# CalibrationBoard.net
KiCad netlist of a schematic drawn in EAGLE
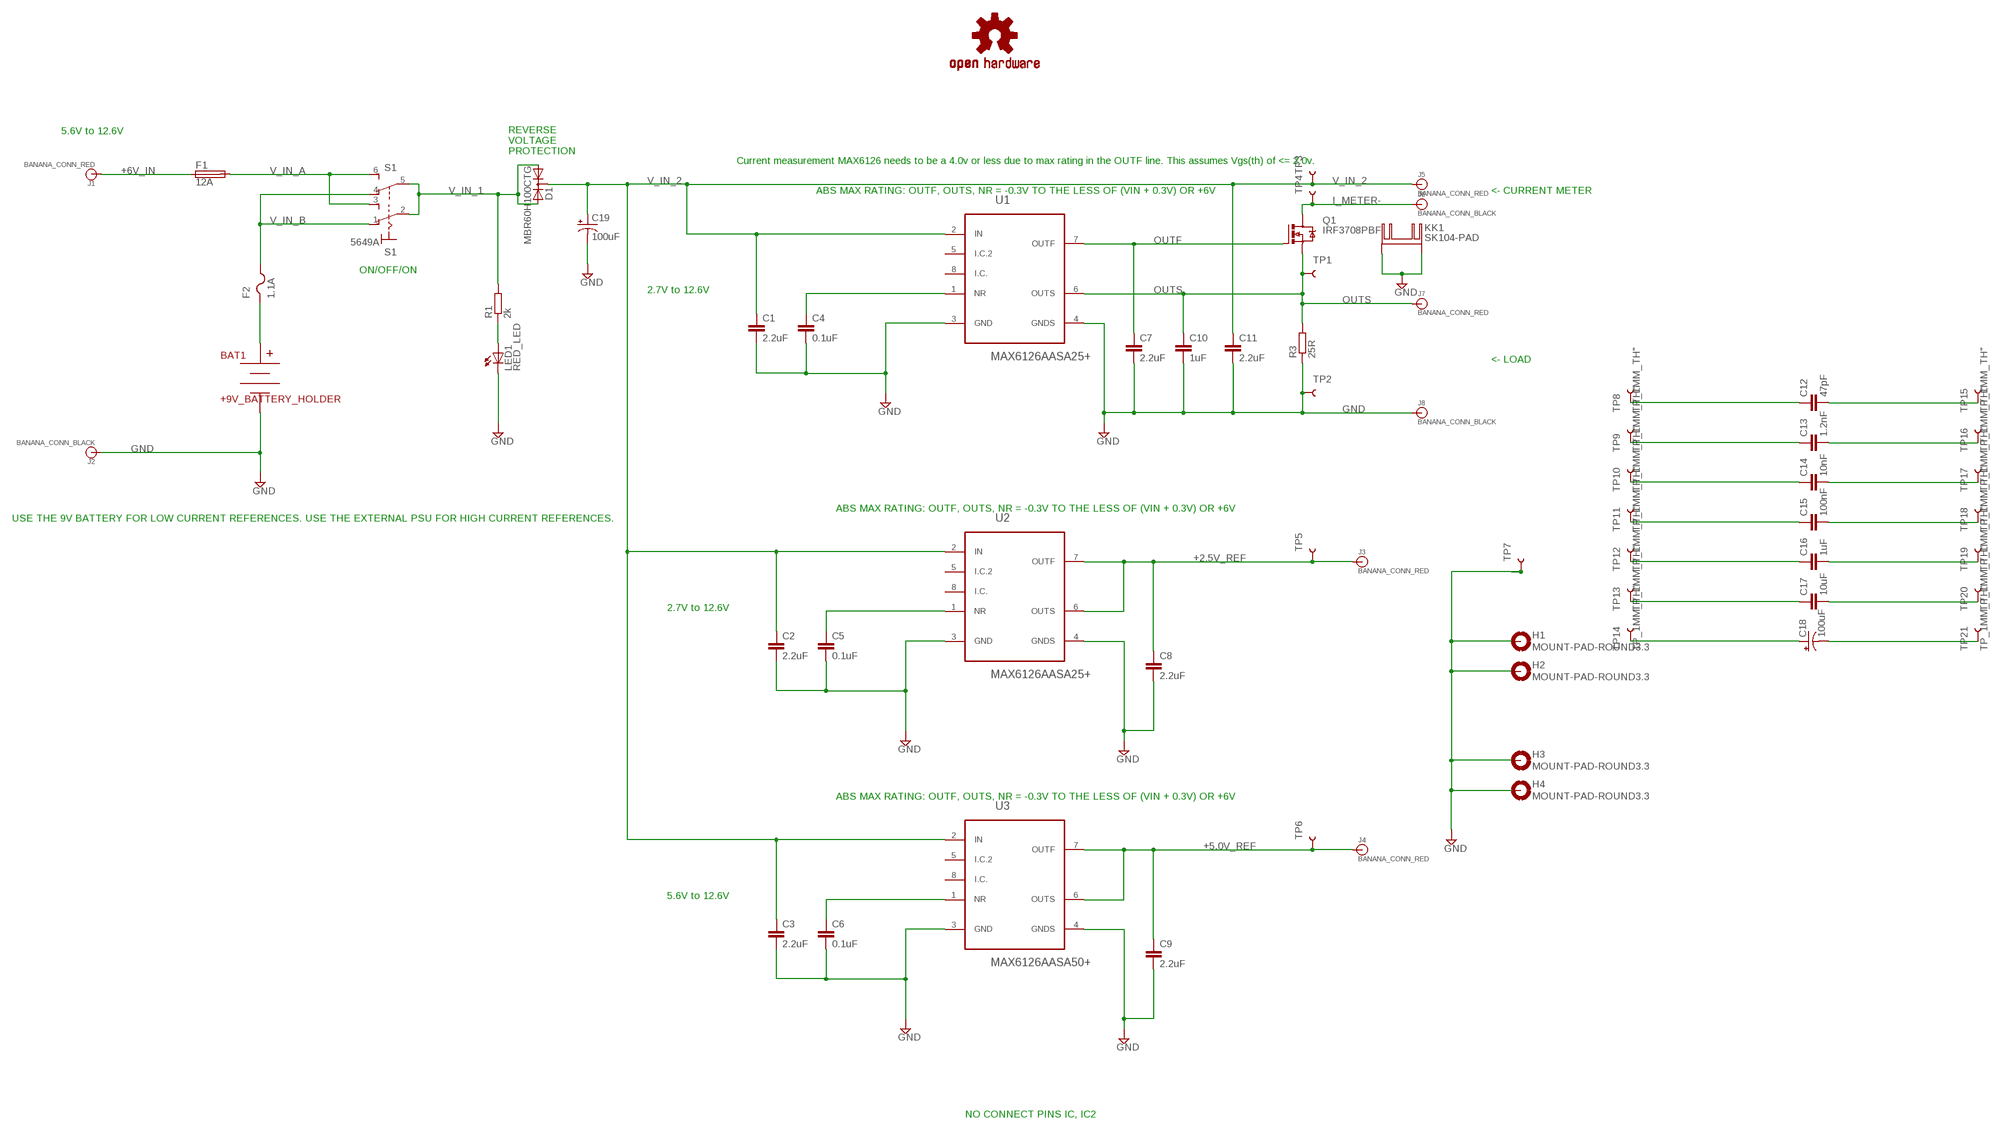
[diagram p0: schematic, sheet 1, part 1 of 2]
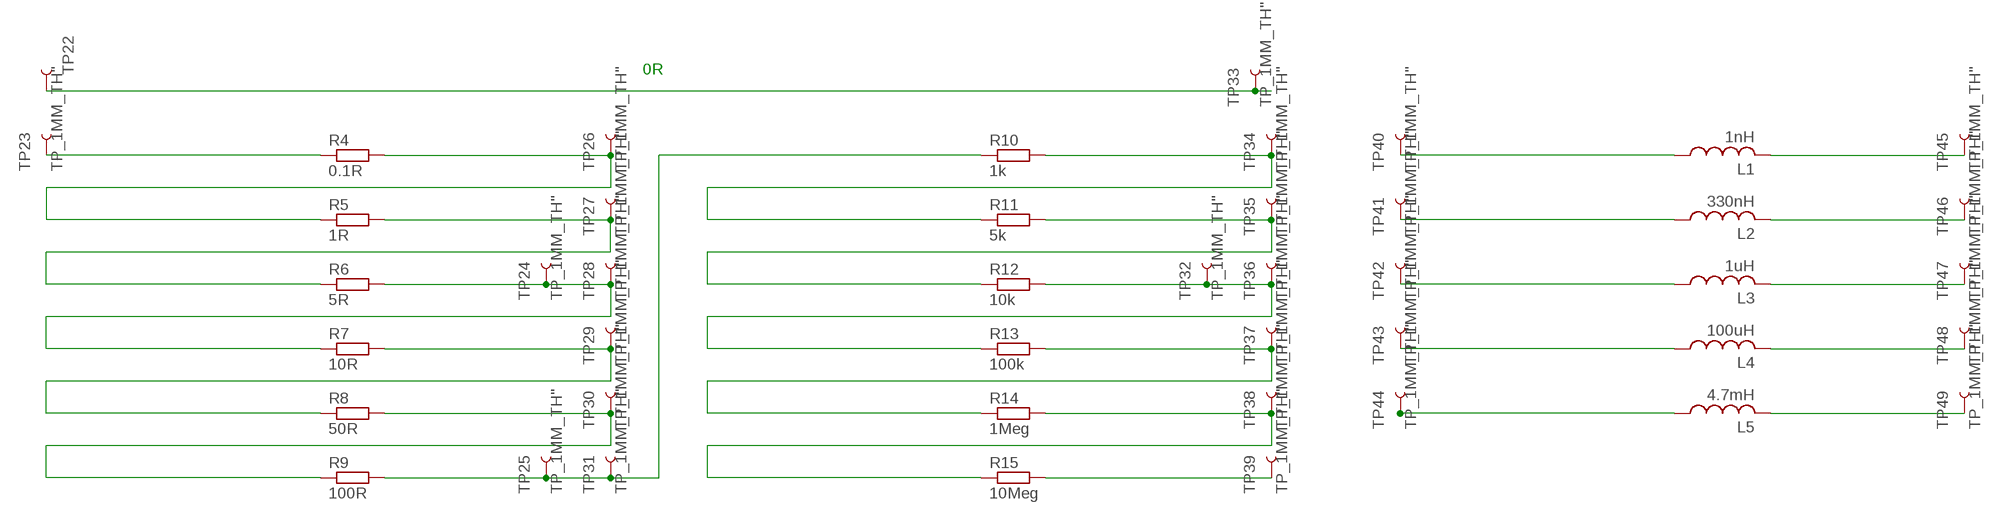
[diagram p1: schematic, sheet 1, part 2 of 2]

(export (version "E")
  (design (tool "Eeschema 10.0.6"))
  (components
    (comp (ref "BAT1")
      (value "+9V_BATTERY_HOLDER")
      (footprint "eagle-import:BC9VPC")
      (libsource (lib "eagle-import") (part "BC9VPC"))
    )
    (comp (ref "C1")
      (value "2.2uF")
      (footprint "eagle-import:C0805")
      (libsource (lib "eagle-import") (part "C-EUC0805"))
    )
    (comp (ref "C2")
      (value "2.2uF")
      (footprint "eagle-import:C0805")
      (libsource (lib "eagle-import") (part "C-EUC0805"))
    )
    (comp (ref "C3")
      (value "2.2uF")
      (footprint "eagle-import:C0805")
      (libsource (lib "eagle-import") (part "C-EUC0805"))
    )
    (comp (ref "C4")
      (value "0.1uF")
      (footprint "eagle-import:C0805")
      (libsource (lib "eagle-import") (part "C-EUC0805"))
    )
    (comp (ref "C5")
      (value "0.1uF")
      (footprint "eagle-import:C0805")
      (libsource (lib "eagle-import") (part "C-EUC0805"))
    )
    (comp (ref "C6")
      (value "0.1uF")
      (footprint "eagle-import:C0805")
      (libsource (lib "eagle-import") (part "C-EUC0805"))
    )
    (comp (ref "C7")
      (value "2.2uF")
      (footprint "eagle-import:C0805")
      (libsource (lib "eagle-import") (part "C-EUC0805"))
    )
    (comp (ref "C8")
      (value "2.2uF")
      (footprint "eagle-import:C0805")
      (libsource (lib "eagle-import") (part "C-EUC0805"))
    )
    (comp (ref "C9")
      (value "2.2uF")
      (footprint "eagle-import:C0805")
      (libsource (lib "eagle-import") (part "C-EUC0805"))
    )
    (comp (ref "C10")
      (value "1uF")
      (footprint "eagle-import:C0805")
      (libsource (lib "eagle-import") (part "C-EUC0805"))
    )
    (comp (ref "C11")
      (value "2.2uF")
      (footprint "eagle-import:C0805")
      (libsource (lib "eagle-import") (part "C-EUC0805"))
    )
    (comp (ref "C12")
      (value "47pF")
      (footprint "eagle-import:C0805")
      (fields (field (name "MF") "AVX") (field (name "MPN") "08052U470FAT2A"))
      (libsource (lib "eagle-import") (part "C-EUC0805"))
    )
    (comp (ref "C13")
      (value "1.2nF")
      (footprint "eagle-import:C0805")
      (fields (field (name "MF") "VISHAY VITRAMON") (field (name "MPN") "VJ0805A122FXBMT"))
      (libsource (lib "eagle-import") (part "C-EUC0805"))
    )
    (comp (ref "C14")
      (value "10nF")
      (footprint "eagle-import:C0805")
      (libsource (lib "eagle-import") (part "C-EUC0805"))
    )
    (comp (ref "C15")
      (value "100nF")
      (footprint "eagle-import:C0805")
      (fields (field (name "MF") "AVX") (field (name "MPN") "08055C104JAT2A"))
      (libsource (lib "eagle-import") (part "C-EUC0805"))
    )
    (comp (ref "C16")
      (value "1uF")
      (footprint "eagle-import:C0805")
      (libsource (lib "eagle-import") (part "C-EUC0805"))
    )
    (comp (ref "C17")
      (value "10uF")
      (footprint "eagle-import:C0805")
      (libsource (lib "eagle-import") (part "C-EUC0805"))
    )
    (comp (ref "C18")
      (value "100uF")
      (footprint "eagle-import:E5-10,5")
      (libsource (lib "eagle-import") (part "CPOL-USE5-10.5"))
    )
    (comp (ref "C19")
      (value "100uF")
      (footprint "eagle-import:E5-10,5")
      (libsource (lib "eagle-import") (part "CPOL-USE5-10.5"))
    )
    (comp (ref "D1")
      (value "MBR60H100CTG")
      (footprint "eagle-import:TO220ABS")
      (fields (field (name "MF") "ON SEMICONDUCTOR"))
      (libsource (lib "eagle-import") (part "DIODE-2AC|CATO220V"))
    )
    (comp (ref "F1")
      (value "12A")
      (footprint "eagle-import:RGEF1200")
      (fields
        (field (name "MF") "TE CONNECTIVITY / RAYCHEM ")
        (field (name "MPN") "RGEF1200")
        (field (name "MF_1") "TE CONNECTIVITY / RAYCHEM")
      )
      (libsource (lib "eagle-import") (part "RGEF1200"))
    )
    (comp (ref "F2")
      (value "1.1A")
      (footprint "eagle-import:1812")
      (fields (field (name "MF") "TE CONNECTIVITY / RAYCHEM") (field (name "MPN") "MINISMDC110F/24-2"))
      (libsource (lib "eagle-import") (part "PTCFUSE-1812"))
    )
    (comp (ref "H1")
      (value "MOUNT-PAD-ROUND3.3")
      (footprint "eagle-import:3,3-PAD")
      (libsource (lib "eagle-import") (part "MOUNT-PAD-ROUND3.3"))
    )
    (comp (ref "H2")
      (value "MOUNT-PAD-ROUND3.3")
      (footprint "eagle-import:3,3-PAD")
      (libsource (lib "eagle-import") (part "MOUNT-PAD-ROUND3.3"))
    )
    (comp (ref "H3")
      (value "MOUNT-PAD-ROUND3.3")
      (footprint "eagle-import:3,3-PAD")
      (libsource (lib "eagle-import") (part "MOUNT-PAD-ROUND3.3"))
    )
    (comp (ref "H4")
      (value "MOUNT-PAD-ROUND3.3")
      (footprint "eagle-import:3,3-PAD")
      (libsource (lib "eagle-import") (part "MOUNT-PAD-ROUND3.3"))
    )
    (comp (ref "J1")
      (value "BANANA_CONN_RED")
      (footprint "eagle-import:BANANA_CONN")
      (fields (field (name "MF") "HIRSCHMANN TEST AND MEASUREMENT") (field (name "MPN") "972354101"))
      (libsource (lib "eagle-import") (part "BANANA_CONN"))
    )
    (comp (ref "J2")
      (value "BANANA_CONN_BLACK")
      (footprint "eagle-import:BANANA_CONN")
      (fields (field (name "MF") "HIRSCHMANN TEST AND MEASUREMENT") (field (name "MPN") "972354101"))
      (libsource (lib "eagle-import") (part "BANANA_CONN"))
    )
    (comp (ref "J3")
      (value "BANANA_CONN_RED")
      (footprint "eagle-import:BANANA_CONN")
      (fields (field (name "MF") "HIRSCHMANN TEST AND MEASUREMENT") (field (name "MPN") "972354101"))
      (libsource (lib "eagle-import") (part "BANANA_CONN"))
    )
    (comp (ref "J4")
      (value "BANANA_CONN_RED")
      (footprint "eagle-import:BANANA_CONN")
      (fields (field (name "MF") "HIRSCHMANN TEST AND MEASUREMENT") (field (name "MPN") "972354101"))
      (libsource (lib "eagle-import") (part "BANANA_CONN"))
    )
    (comp (ref "J5")
      (value "BANANA_CONN_RED")
      (footprint "eagle-import:BANANA_CONN")
      (fields (field (name "MF") "HIRSCHMANN TEST AND MEASUREMENT") (field (name "MPN") "972354101"))
      (libsource (lib "eagle-import") (part "BANANA_CONN"))
    )
    (comp (ref "J6")
      (value "BANANA_CONN_BLACK")
      (footprint "eagle-import:BANANA_CONN")
      (fields (field (name "MF") "HIRSCHMANN TEST AND MEASUREMENT") (field (name "MPN") "972354101"))
      (libsource (lib "eagle-import") (part "BANANA_CONN"))
    )
    (comp (ref "J7")
      (value "BANANA_CONN_RED")
      (footprint "eagle-import:BANANA_CONN")
      (fields (field (name "MF") "HIRSCHMANN TEST AND MEASUREMENT") (field (name "MPN") "972354101"))
      (libsource (lib "eagle-import") (part "BANANA_CONN"))
    )
    (comp (ref "J8")
      (value "BANANA_CONN_BLACK")
      (footprint "eagle-import:BANANA_CONN")
      (fields (field (name "MF") "HIRSCHMANN TEST AND MEASUREMENT") (field (name "MPN") "972354101"))
      (libsource (lib "eagle-import") (part "BANANA_CONN"))
    )
    (comp (ref "KK1")
      (value "SK104-PAD")
      (footprint "eagle-import:SK104-PAD")
      (fields (field (name "MF") "FISCHER ELEKTRONIK") (field (name "MPN") "SK 129 38,1 STS"))
      (libsource (lib "eagle-import") (part "SK104-PAD"))
    )
    (comp (ref "L1")
      (value "1nH")
      (footprint "eagle-import:L1812")
      (libsource (lib "eagle-import") (part "L-USL1812"))
    )
    (comp (ref "L2")
      (value "330nH")
      (footprint "eagle-import:L2825P")
      (fields (field (name "MF") "BOURNS") (field (name "MPN") "CW252016-R33G"))
      (libsource (lib "eagle-import") (part "L-USL2825P"))
    )
    (comp (ref "L3")
      (value "1uH")
      (footprint "eagle-import:L1812")
      (fields (field (name "MF") "COILCRAFT") (field (name "MPN") "1812PS-102JLC"))
      (libsource (lib "eagle-import") (part "L-USL1812"))
    )
    (comp (ref "L4")
      (value "100uH")
      (footprint "eagle-import:L1812")
      (fields (field (name "MF") "COILCRAFT") (field (name "MPN") "1812PS-104JLB"))
      (libsource (lib "eagle-import") (part "L-USL1812"))
    )
    (comp (ref "L5")
      (value "4.7mH")
      (footprint "eagle-import:6000-XXXX-RC")
      (fields (field (name "MF") "WURTH ELEKTRONIK") (field (name "MPN") "7447721047"))
      (libsource (lib "eagle-import") (part "L-US6000-XXX-RC"))
    )
    (comp (ref "LED1")
      (value "RED_LED")
      (footprint "eagle-import:P-LCC-2")
      (fields (field (name "MF") "DIALIGHT") (field (name "MPN") "597-3121-207F"))
      (libsource (lib "eagle-import") (part "LEDP-LCC-2"))
    )
    (comp (ref "LOGO1")
      (value "OSHW-LOGOL")
      (footprint "eagle-import:OSHW-LOGO-L")
      (libsource (lib "eagle-import") (part "OSHW-LOGOL"))
    )
    (comp (ref "Q1")
      (value "IRF3708PBF")
      (footprint "eagle-import:TO220BV")
      (fields (field (name "MF") "INTERNATIONAL RECTIFIER"))
      (libsource (lib "eagle-import") (part "IRF540"))
    )
    (comp (ref "R1")
      (value "2k")
      (footprint "eagle-import:R0805")
      (libsource (lib "eagle-import") (part "R-EU_R0805"))
    )
    (comp (ref "R3")
      (value "25R")
      (footprint "eagle-import:R0805")
      (libsource (lib "eagle-import") (part "R-EU_R0805"))
    )
    (comp (ref "R4")
      (value "0.1R")
      (footprint "eagle-import:R0805")
      (fields (field (name "MF") "PANASONIC ELECTRONIC COMPONENTS") (field (name "MPN") "ERJ6RSFR10V"))
      (libsource (lib "eagle-import") (part "R-EU_R0805"))
    )
    (comp (ref "R5")
      (value "1R")
      (footprint "eagle-import:R0805")
      (fields (field (name "MF") "BOURNS") (field (name "MPN") "CR0805-FX-1R00ELF"))
      (libsource (lib "eagle-import") (part "R-EU_R0805"))
    )
    (comp (ref "R6")
      (value "5R")
      (footprint "eagle-import:R0805")
      (libsource (lib "eagle-import") (part "R-EU_R0805"))
    )
    (comp (ref "R7")
      (value "10R")
      (footprint "eagle-import:R0805")
      (fields (field (name "MF") "BOURNS") (field (name "MPN") "CRT0805-BY-10R0ELF"))
      (libsource (lib "eagle-import") (part "R-EU_R0805"))
    )
    (comp (ref "R8")
      (value "50R")
      (footprint "eagle-import:R0805")
      (libsource (lib "eagle-import") (part "R-EU_R0805"))
    )
    (comp (ref "R9")
      (value "100R")
      (footprint "eagle-import:R0805")
      (fields (field (name "MF") "SUSUMU") (field (name "MPN") "RR1220P-101-B-T5"))
      (libsource (lib "eagle-import") (part "R-EU_R0805"))
    )
    (comp (ref "R10")
      (value "1k")
      (footprint "eagle-import:R0805")
      (fields (field (name "MF") "PANASONIC ELECTRONIC COMPONENTS") (field (name "MPN") "ERA6AEB102V"))
      (libsource (lib "eagle-import") (part "R-EU_R0805"))
    )
    (comp (ref "R11")
      (value "5k")
      (footprint "eagle-import:R0805")
      (libsource (lib "eagle-import") (part "R-EU_R0805"))
    )
    (comp (ref "R12")
      (value "10k")
      (footprint "eagle-import:R0805")
      (fields (field (name "MF") "SUSUMU") (field (name "MPN") "RR1220P-103-B-T5"))
      (libsource (lib "eagle-import") (part "R-EU_R0805"))
    )
    (comp (ref "R13")
      (value "100k")
      (footprint "eagle-import:R0805")
      (fields (field (name "MF") "SUSUMU") (field (name "MPN") "RR1220P-104-B-T5"))
      (libsource (lib "eagle-import") (part "R-EU_R0805"))
    )
    (comp (ref "R14")
      (value "1Meg")
      (footprint "eagle-import:R0805")
      (fields (field (name "MF") "SUSUMU") (field (name "MPN") "RR1220P-105-B-T5"))
      (libsource (lib "eagle-import") (part "R-EU_R0805"))
    )
    (comp (ref "R15")
      (value "10Meg")
      (footprint "eagle-import:R0805")
      (libsource (lib "eagle-import") (part "R-EU_R0805"))
    )
    (comp (ref "S1")
      (value "5649A")
      (footprint "eagle-import:320-938")
      (fields (field (name "MF") "APEM") (field (name "MPN") "5649A") (field (name "OC_FARNELL") "1082316"))
      (libsource (lib "eagle-import") (part "320-938"))
    )
    (comp (ref "TP1")
      (value "TP_1MM_TH\"")
      (footprint "eagle-import:TP_1MM_TH")
      (fields (field (name "MF") "MULTICOMP") (field (name "MPN") "TEST-3"))
      (libsource (lib "eagle-import") (part "TP_1MM_TH{dblquote}"))
    )
    (comp (ref "TP2")
      (value "TP_1MM_TH\"")
      (footprint "eagle-import:TP_1MM_TH")
      (fields (field (name "MF") "MULTICOMP") (field (name "MPN") "TEST-3"))
      (libsource (lib "eagle-import") (part "TP_1MM_TH{dblquote}"))
    )
    (comp (ref "TP3")
      (value "TP_1MM_TH\"")
      (footprint "eagle-import:TP_1MM_TH")
      (fields (field (name "MF") "MULTICOMP") (field (name "MPN") "TEST-3"))
      (libsource (lib "eagle-import") (part "TP_1MM_TH{dblquote}"))
    )
    (comp (ref "TP4")
      (value "TP_1MM_TH\"")
      (footprint "eagle-import:TP_1MM_TH")
      (fields (field (name "MF") "MULTICOMP") (field (name "MPN") "TEST-3"))
      (libsource (lib "eagle-import") (part "TP_1MM_TH{dblquote}"))
    )
    (comp (ref "TP5")
      (value "TP_1MM_TH\"")
      (footprint "eagle-import:TP_1MM_TH")
      (fields (field (name "MF") "MULTICOMP") (field (name "MPN") "TEST-3"))
      (libsource (lib "eagle-import") (part "TP_1MM_TH{dblquote}"))
    )
    (comp (ref "TP6")
      (value "TP_1MM_TH\"")
      (footprint "eagle-import:TP_1MM_TH")
      (fields (field (name "MF") "MULTICOMP") (field (name "MPN") "TEST-3"))
      (libsource (lib "eagle-import") (part "TP_1MM_TH{dblquote}"))
    )
    (comp (ref "TP7")
      (value "TP_1MM_TH\"")
      (footprint "eagle-import:TP_1MM_TH")
      (fields (field (name "MF") "MULTICOMP") (field (name "MPN") "TEST-3"))
      (libsource (lib "eagle-import") (part "TP_1MM_TH{dblquote}"))
    )
    (comp (ref "TP8")
      (value "TP_1MM_TH\"")
      (footprint "eagle-import:TP_1MM_TH")
      (fields (field (name "MF") "MULTICOMP") (field (name "MPN") "TEST-3"))
      (libsource (lib "eagle-import") (part "TP_1MM_TH{dblquote}"))
    )
    (comp (ref "TP9")
      (value "TP_1MM_TH\"")
      (footprint "eagle-import:TP_1MM_TH")
      (fields (field (name "MF") "MULTICOMP") (field (name "MPN") "TEST-3"))
      (libsource (lib "eagle-import") (part "TP_1MM_TH{dblquote}"))
    )
    (comp (ref "TP10")
      (value "TP_1MM_TH\"")
      (footprint "eagle-import:TP_1MM_TH")
      (fields (field (name "MF") "MULTICOMP") (field (name "MPN") "TEST-3"))
      (libsource (lib "eagle-import") (part "TP_1MM_TH{dblquote}"))
    )
    (comp (ref "TP11")
      (value "TP_1MM_TH\"")
      (footprint "eagle-import:TP_1MM_TH")
      (fields (field (name "MF") "MULTICOMP") (field (name "MPN") "TEST-3"))
      (libsource (lib "eagle-import") (part "TP_1MM_TH{dblquote}"))
    )
    (comp (ref "TP12")
      (value "TP_1MM_TH\"")
      (footprint "eagle-import:TP_1MM_TH")
      (fields (field (name "MF") "MULTICOMP") (field (name "MPN") "TEST-3"))
      (libsource (lib "eagle-import") (part "TP_1MM_TH{dblquote}"))
    )
    (comp (ref "TP13")
      (value "TP_1MM_TH\"")
      (footprint "eagle-import:TP_1MM_TH")
      (fields (field (name "MF") "MULTICOMP") (field (name "MPN") "TEST-3"))
      (libsource (lib "eagle-import") (part "TP_1MM_TH{dblquote}"))
    )
    (comp (ref "TP14")
      (value "TP_1MM_TH\"")
      (footprint "eagle-import:TP_1MM_TH")
      (fields (field (name "MF") "MULTICOMP") (field (name "MPN") "TEST-3"))
      (libsource (lib "eagle-import") (part "TP_1MM_TH{dblquote}"))
    )
    (comp (ref "TP15")
      (value "TP_1MM_TH\"")
      (footprint "eagle-import:TP_1MM_TH")
      (fields (field (name "MF") "MULTICOMP") (field (name "MPN") "TEST-3"))
      (libsource (lib "eagle-import") (part "TP_1MM_TH{dblquote}"))
    )
    (comp (ref "TP16")
      (value "TP_1MM_TH\"")
      (footprint "eagle-import:TP_1MM_TH")
      (fields (field (name "MF") "MULTICOMP") (field (name "MPN") "TEST-3"))
      (libsource (lib "eagle-import") (part "TP_1MM_TH{dblquote}"))
    )
    (comp (ref "TP17")
      (value "TP_1MM_TH\"")
      (footprint "eagle-import:TP_1MM_TH")
      (fields (field (name "MF") "MULTICOMP") (field (name "MPN") "TEST-3"))
      (libsource (lib "eagle-import") (part "TP_1MM_TH{dblquote}"))
    )
    (comp (ref "TP18")
      (value "TP_1MM_TH\"")
      (footprint "eagle-import:TP_1MM_TH")
      (fields (field (name "MF") "MULTICOMP") (field (name "MPN") "TEST-3"))
      (libsource (lib "eagle-import") (part "TP_1MM_TH{dblquote}"))
    )
    (comp (ref "TP19")
      (value "TP_1MM_TH\"")
      (footprint "eagle-import:TP_1MM_TH")
      (fields (field (name "MF") "MULTICOMP") (field (name "MPN") "TEST-3"))
      (libsource (lib "eagle-import") (part "TP_1MM_TH{dblquote}"))
    )
    (comp (ref "TP20")
      (value "TP_1MM_TH\"")
      (footprint "eagle-import:TP_1MM_TH")
      (fields (field (name "MF") "MULTICOMP") (field (name "MPN") "TEST-3"))
      (libsource (lib "eagle-import") (part "TP_1MM_TH{dblquote}"))
    )
    (comp (ref "TP21")
      (value "TP_1MM_TH\"")
      (footprint "eagle-import:TP_1MM_TH")
      (fields (field (name "MF") "MULTICOMP") (field (name "MPN") "TEST-3"))
      (libsource (lib "eagle-import") (part "TP_1MM_TH{dblquote}"))
    )
    (comp (ref "TP22")
      (value "TP_1MM_TH\"")
      (footprint "eagle-import:TP_1MM_TH")
      (fields (field (name "MF") "MULTICOMP") (field (name "MPN") "TEST-3"))
      (libsource (lib "eagle-import") (part "TP_1MM_TH{dblquote}"))
    )
    (comp (ref "TP23")
      (value "TP_1MM_TH\"")
      (footprint "eagle-import:TP_1MM_TH")
      (fields (field (name "MF") "MULTICOMP") (field (name "MPN") "TEST-3"))
      (libsource (lib "eagle-import") (part "TP_1MM_TH{dblquote}"))
    )
    (comp (ref "TP24")
      (value "TP_1MM_TH\"")
      (footprint "eagle-import:TP_1MM_TH")
      (fields (field (name "MF") "MULTICOMP") (field (name "MPN") "TEST-3"))
      (libsource (lib "eagle-import") (part "TP_1MM_TH{dblquote}"))
    )
    (comp (ref "TP25")
      (value "TP_1MM_TH\"")
      (footprint "eagle-import:TP_1MM_TH")
      (fields (field (name "MF") "MULTICOMP") (field (name "MPN") "TEST-3"))
      (libsource (lib "eagle-import") (part "TP_1MM_TH{dblquote}"))
    )
    (comp (ref "TP26")
      (value "TP_1MM_TH\"")
      (footprint "eagle-import:TP_1MM_TH")
      (fields (field (name "MF") "MULTICOMP") (field (name "MPN") "TEST-3"))
      (libsource (lib "eagle-import") (part "TP_1MM_TH{dblquote}"))
    )
    (comp (ref "TP27")
      (value "TP_1MM_TH\"")
      (footprint "eagle-import:TP_1MM_TH")
      (fields (field (name "MF") "MULTICOMP") (field (name "MPN") "TEST-3"))
      (libsource (lib "eagle-import") (part "TP_1MM_TH{dblquote}"))
    )
    (comp (ref "TP28")
      (value "TP_1MM_TH\"")
      (footprint "eagle-import:TP_1MM_TH")
      (fields (field (name "MF") "MULTICOMP") (field (name "MPN") "TEST-3"))
      (libsource (lib "eagle-import") (part "TP_1MM_TH{dblquote}"))
    )
    (comp (ref "TP29")
      (value "TP_1MM_TH\"")
      (footprint "eagle-import:TP_1MM_TH")
      (fields (field (name "MF") "MULTICOMP") (field (name "MPN") "TEST-3"))
      (libsource (lib "eagle-import") (part "TP_1MM_TH{dblquote}"))
    )
    (comp (ref "TP30")
      (value "TP_1MM_TH\"")
      (footprint "eagle-import:TP_1MM_TH")
      (fields (field (name "MF") "MULTICOMP") (field (name "MPN") "TEST-3"))
      (libsource (lib "eagle-import") (part "TP_1MM_TH{dblquote}"))
    )
    (comp (ref "TP31")
      (value "TP_1MM_TH\"")
      (footprint "eagle-import:TP_1MM_TH")
      (fields (field (name "MF") "MULTICOMP") (field (name "MPN") "TEST-3"))
      (libsource (lib "eagle-import") (part "TP_1MM_TH{dblquote}"))
    )
    (comp (ref "TP32")
      (value "TP_1MM_TH\"")
      (footprint "eagle-import:TP_1MM_TH")
      (fields (field (name "MF") "MULTICOMP") (field (name "MPN") "TEST-3"))
      (libsource (lib "eagle-import") (part "TP_1MM_TH{dblquote}"))
    )
    (comp (ref "TP33")
      (value "TP_1MM_TH\"")
      (footprint "eagle-import:TP_1MM_TH")
      (fields (field (name "MF") "MULTICOMP") (field (name "MPN") "TEST-3"))
      (libsource (lib "eagle-import") (part "TP_1MM_TH{dblquote}"))
    )
    (comp (ref "TP34")
      (value "TP_1MM_TH\"")
      (footprint "eagle-import:TP_1MM_TH")
      (fields (field (name "MF") "MULTICOMP") (field (name "MPN") "TEST-3"))
      (libsource (lib "eagle-import") (part "TP_1MM_TH{dblquote}"))
    )
    (comp (ref "TP35")
      (value "TP_1MM_TH\"")
      (footprint "eagle-import:TP_1MM_TH")
      (fields (field (name "MF") "MULTICOMP") (field (name "MPN") "TEST-3"))
      (libsource (lib "eagle-import") (part "TP_1MM_TH{dblquote}"))
    )
    (comp (ref "TP36")
      (value "TP_1MM_TH\"")
      (footprint "eagle-import:TP_1MM_TH")
      (fields (field (name "MF") "MULTICOMP") (field (name "MPN") "TEST-3"))
      (libsource (lib "eagle-import") (part "TP_1MM_TH{dblquote}"))
    )
    (comp (ref "TP37")
      (value "TP_1MM_TH\"")
      (footprint "eagle-import:TP_1MM_TH")
      (fields (field (name "MF") "MULTICOMP") (field (name "MPN") "TEST-3"))
      (libsource (lib "eagle-import") (part "TP_1MM_TH{dblquote}"))
    )
    (comp (ref "TP38")
      (value "TP_1MM_TH\"")
      (footprint "eagle-import:TP_1MM_TH")
      (fields (field (name "MF") "MULTICOMP") (field (name "MPN") "TEST-3"))
      (libsource (lib "eagle-import") (part "TP_1MM_TH{dblquote}"))
    )
    (comp (ref "TP39")
      (value "TP_1MM_TH\"")
      (footprint "eagle-import:TP_1MM_TH")
      (fields (field (name "MF") "MULTICOMP") (field (name "MPN") "TEST-3"))
      (libsource (lib "eagle-import") (part "TP_1MM_TH{dblquote}"))
    )
    (comp (ref "TP40")
      (value "TP_1MM_TH\"")
      (footprint "eagle-import:TP_1MM_TH")
      (fields (field (name "MF") "MULTICOMP") (field (name "MPN") "TEST-3"))
      (libsource (lib "eagle-import") (part "TP_1MM_TH{dblquote}"))
    )
    (comp (ref "TP41")
      (value "TP_1MM_TH\"")
      (footprint "eagle-import:TP_1MM_TH")
      (fields (field (name "MF") "MULTICOMP") (field (name "MPN") "TEST-3"))
      (libsource (lib "eagle-import") (part "TP_1MM_TH{dblquote}"))
    )
    (comp (ref "TP42")
      (value "TP_1MM_TH\"")
      (footprint "eagle-import:TP_1MM_TH")
      (fields (field (name "MF") "MULTICOMP") (field (name "MPN") "TEST-3"))
      (libsource (lib "eagle-import") (part "TP_1MM_TH{dblquote}"))
    )
    (comp (ref "TP43")
      (value "TP_1MM_TH\"")
      (footprint "eagle-import:TP_1MM_TH")
      (fields (field (name "MF") "MULTICOMP") (field (name "MPN") "TEST-3"))
      (libsource (lib "eagle-import") (part "TP_1MM_TH{dblquote}"))
    )
    (comp (ref "TP44")
      (value "TP_1MM_TH\"")
      (footprint "eagle-import:TP_1MM_TH")
      (fields (field (name "MF") "MULTICOMP") (field (name "MPN") "TEST-3"))
      (libsource (lib "eagle-import") (part "TP_1MM_TH{dblquote}"))
    )
    (comp (ref "TP45")
      (value "TP_1MM_TH\"")
      (footprint "eagle-import:TP_1MM_TH")
      (fields (field (name "MF") "MULTICOMP") (field (name "MPN") "TEST-3"))
      (libsource (lib "eagle-import") (part "TP_1MM_TH{dblquote}"))
    )
    (comp (ref "TP46")
      (value "TP_1MM_TH\"")
      (footprint "eagle-import:TP_1MM_TH")
      (fields (field (name "MF") "MULTICOMP") (field (name "MPN") "TEST-3"))
      (libsource (lib "eagle-import") (part "TP_1MM_TH{dblquote}"))
    )
    (comp (ref "TP47")
      (value "TP_1MM_TH\"")
      (footprint "eagle-import:TP_1MM_TH")
      (fields (field (name "MF") "MULTICOMP") (field (name "MPN") "TEST-3"))
      (libsource (lib "eagle-import") (part "TP_1MM_TH{dblquote}"))
    )
    (comp (ref "TP48")
      (value "TP_1MM_TH\"")
      (footprint "eagle-import:TP_1MM_TH")
      (fields (field (name "MF") "MULTICOMP") (field (name "MPN") "TEST-3"))
      (libsource (lib "eagle-import") (part "TP_1MM_TH{dblquote}"))
    )
    (comp (ref "TP49")
      (value "TP_1MM_TH\"")
      (footprint "eagle-import:TP_1MM_TH")
      (fields (field (name "MF") "MULTICOMP") (field (name "MPN") "TEST-3"))
      (libsource (lib "eagle-import") (part "TP_1MM_TH{dblquote}"))
    )
    (comp (ref "U1")
      (value "MAX6126AASA25+")
      (footprint "eagle-import:SOIC127P600X175-8N")
      (fields
        (field (name "MPN") "MAX6126AASA50+")
        (field (name "MF") "MAXIM INTEGRATED PRODUCTS")
        (field (name "MPN_1") "MAX6126AASA25+")
        (field (name "OC_FARNELL") "1673170")
      )
      (libsource (lib "eagle-import") (part "MAX6126AASA50+"))
    )
    (comp (ref "U2")
      (value "MAX6126AASA25+")
      (footprint "eagle-import:SOIC127P600X175-8N")
      (fields
        (field (name "MPN") "MAX6126AASA50+")
        (field (name "MF") "MAXIM INTEGRATED PRODUCTS")
        (field (name "MPN_1") "MAX6126AASA25+")
        (field (name "OC_FARNELL") "1673170")
      )
      (libsource (lib "eagle-import") (part "MAX6126AASA50+"))
    )
    (comp (ref "U3")
      (value "MAX6126AASA50+")
      (footprint "eagle-import:SOIC127P600X175-8N")
      (fields (field (name "OC_FARNELL") "unknown"))
      (libsource (lib "eagle-import") (part "MAX6126AASA50+"))
    )
  )
  (nets
    (net (code "1") (name "/+2.5V_REF") (class "Default")
      (node (ref "C8") (pin "1") (pinfunction "1_1") (pintype "passive"))
      (node (ref "J3") (pin "P$1") (pinfunction "1_P$1") (pintype "passive"))
      (node (ref "TP5") (pin "P$1") (pinfunction "1_P$1") (pintype "bidirectional"))
      (node (ref "U2") (pin "6") (pinfunction "OUTS_6") (pintype "output"))
      (node (ref "U2") (pin "7") (pinfunction "OUTF_7") (pintype "passive"))
    )
    (net (code "2") (name "/+5.0V_REF") (class "Default")
      (node (ref "C9") (pin "1") (pinfunction "1_1") (pintype "passive"))
      (node (ref "J4") (pin "P$1") (pinfunction "1_P$1") (pintype "passive"))
      (node (ref "TP6") (pin "P$1") (pinfunction "1_P$1") (pintype "bidirectional"))
      (node (ref "U3") (pin "6") (pinfunction "OUTS_6") (pintype "output"))
      (node (ref "U3") (pin "7") (pinfunction "OUTF_7") (pintype "passive"))
    )
    (net (code "3") (name "/+6V_IN") (class "Default")
      (node (ref "F1") (pin "1") (pinfunction "1_1") (pintype "passive"))
      (node (ref "J1") (pin "P$1") (pinfunction "1_P$1") (pintype "passive"))
    )
    (net (code "4") (name "/I_METER-") (class "Default")
      (node (ref "J6") (pin "P$1") (pinfunction "1_P$1") (pintype "passive"))
      (node (ref "Q1") (pin "D") (pinfunction "D_D") (pintype "passive"))
      (node (ref "TP4") (pin "P$1") (pinfunction "1_P$1") (pintype "bidirectional"))
    )
    (net (code "5") (name "/OUTF") (class "Default")
      (node (ref "C7") (pin "1") (pinfunction "1_1") (pintype "passive"))
      (node (ref "Q1") (pin "G") (pinfunction "G_G") (pintype "passive"))
      (node (ref "U1") (pin "7") (pinfunction "OUTF_7") (pintype "passive"))
    )
    (net (code "6") (name "/OUTS") (class "Default")
      (node (ref "C10") (pin "1") (pinfunction "1_1") (pintype "passive"))
      (node (ref "J7") (pin "P$1") (pinfunction "1_P$1") (pintype "passive"))
      (node (ref "Q1") (pin "S") (pinfunction "S_S") (pintype "passive"))
      (node (ref "R3") (pin "2") (pinfunction "2_2") (pintype "passive"))
      (node (ref "TP1") (pin "P$1") (pinfunction "1_P$1") (pintype "bidirectional"))
      (node (ref "U1") (pin "6") (pinfunction "OUTS_6") (pintype "output"))
    )
    (net (code "7") (name "/V_IN_1") (class "Default")
      (node (ref "D1") (pin "A1") (pinfunction "A1_A1") (pintype "passive"))
      (node (ref "D1") (pin "A2") (pinfunction "A2_A2") (pintype "passive"))
      (node (ref "R1") (pin "2") (pinfunction "2_2") (pintype "passive"))
      (node (ref "S1") (pin "2") (pinfunction "P_2") (pintype "passive"))
      (node (ref "S1") (pin "5") (pinfunction "P_5") (pintype "passive"))
    )
    (net (code "8") (name "/V_IN_2") (class "Default")
      (node (ref "C1") (pin "1") (pinfunction "1_1") (pintype "passive"))
      (node (ref "C11") (pin "1") (pinfunction "1_1") (pintype "passive"))
      (node (ref "C19") (pin "+") (pinfunction "+_+") (pintype "passive"))
      (node (ref "C2") (pin "1") (pinfunction "1_1") (pintype "passive"))
      (node (ref "C3") (pin "1") (pinfunction "1_1") (pintype "passive"))
      (node (ref "D1") (pin "C") (pinfunction "C_C") (pintype "passive"))
      (node (ref "J5") (pin "P$1") (pinfunction "1_P$1") (pintype "passive"))
      (node (ref "TP3") (pin "P$1") (pinfunction "1_P$1") (pintype "bidirectional"))
      (node (ref "U1") (pin "2") (pinfunction "IN_2") (pintype "input"))
      (node (ref "U2") (pin "2") (pinfunction "IN_2") (pintype "input"))
      (node (ref "U3") (pin "2") (pinfunction "IN_2") (pintype "input"))
    )
    (net (code "9") (name "/V_IN_A") (class "Default")
      (node (ref "F1") (pin "2") (pinfunction "2_2") (pintype "passive"))
      (node (ref "S1") (pin "3") (pinfunction "S_3") (pintype "passive"))
      (node (ref "S1") (pin "6") (pinfunction "S_6") (pintype "passive"))
    )
    (net (code "10") (name "/V_IN_B") (class "Default")
      (node (ref "F2") (pin "2") (pinfunction "2_2") (pintype "passive"))
      (node (ref "S1") (pin "1") (pinfunction "O_1") (pintype "passive"))
      (node (ref "S1") (pin "4") (pinfunction "O_4") (pintype "passive"))
    )
    (net (code "11") (name "GND") (class "Default")
      (node (ref "BAT1") (pin "V-") (pinfunction "V-_V-") (pintype "bidirectional"))
      (node (ref "C1") (pin "2") (pinfunction "2_2") (pintype "passive"))
      (node (ref "C10") (pin "2") (pinfunction "2_2") (pintype "passive"))
      (node (ref "C11") (pin "2") (pinfunction "2_2") (pintype "passive"))
      (node (ref "C19") (pin "-") (pinfunction "-_-") (pintype "passive"))
      (node (ref "C2") (pin "2") (pinfunction "2_2") (pintype "passive"))
      (node (ref "C3") (pin "2") (pinfunction "2_2") (pintype "passive"))
      (node (ref "C4") (pin "2") (pinfunction "2_2") (pintype "passive"))
      (node (ref "C5") (pin "2") (pinfunction "2_2") (pintype "passive"))
      (node (ref "C6") (pin "2") (pinfunction "2_2") (pintype "passive"))
      (node (ref "C7") (pin "2") (pinfunction "2_2") (pintype "passive"))
      (node (ref "C8") (pin "2") (pinfunction "2_2") (pintype "passive"))
      (node (ref "C9") (pin "2") (pinfunction "2_2") (pintype "passive"))
      (node (ref "H1") (pin "B3,3") (pinfunction "MOUNT_B3,3") (pintype "passive"))
      (node (ref "H2") (pin "B3,3") (pinfunction "MOUNT_B3,3") (pintype "passive"))
      (node (ref "H3") (pin "B3,3") (pinfunction "MOUNT_B3,3") (pintype "passive"))
      (node (ref "H4") (pin "B3,3") (pinfunction "MOUNT_B3,3") (pintype "passive"))
      (node (ref "J2") (pin "P$1") (pinfunction "1_P$1") (pintype "passive"))
      (node (ref "J8") (pin "P$1") (pinfunction "1_P$1") (pintype "passive"))
      (node (ref "KK1") (pin "K1") (pinfunction "K_K1") (pintype "passive"))
      (node (ref "KK1") (pin "K2") (pinfunction "K_K2") (pintype "passive"))
      (node (ref "LED1") (pin "C") (pinfunction "C_C") (pintype "passive"))
      (node (ref "R3") (pin "1") (pinfunction "1_1") (pintype "passive"))
      (node (ref "TP2") (pin "P$1") (pinfunction "1_P$1") (pintype "bidirectional"))
      (node (ref "TP7") (pin "P$1") (pinfunction "1_P$1") (pintype "bidirectional"))
      (node (ref "U1") (pin "3") (pinfunction "GND_3") (pintype "input"))
      (node (ref "U1") (pin "4") (pinfunction "GNDS_4") (pintype "passive"))
      (node (ref "U2") (pin "3") (pinfunction "GND_3") (pintype "input"))
      (node (ref "U2") (pin "4") (pinfunction "GNDS_4") (pintype "passive"))
      (node (ref "U3") (pin "3") (pinfunction "GND_3") (pintype "input"))
      (node (ref "U3") (pin "4") (pinfunction "GNDS_4") (pintype "passive"))
    )
    (net (code "12") (name "Net-(BAT1-PadV+)") (class "Default")
      (node (ref "BAT1") (pin "V+") (pinfunction "V+_V+") (pintype "bidirectional"))
      (node (ref "F2") (pin "1") (pinfunction "1_1") (pintype "passive"))
    )
    (net (code "13") (name "Net-(LED1-PadA)") (class "Default")
      (node (ref "LED1") (pin "A") (pinfunction "A_A") (pintype "passive"))
      (node (ref "R1") (pin "1") (pinfunction "1_1") (pintype "passive"))
    )
    (net (code "14") (name "Net-(TP8-1)") (class "Default")
      (node (ref "C12") (pin "1") (pinfunction "1_1") (pintype "passive"))
      (node (ref "TP8") (pin "P$1") (pinfunction "1_P$1") (pintype "bidirectional"))
    )
    (net (code "15") (name "Net-(TP9-1)") (class "Default")
      (node (ref "C13") (pin "1") (pinfunction "1_1") (pintype "passive"))
      (node (ref "TP9") (pin "P$1") (pinfunction "1_P$1") (pintype "bidirectional"))
    )
    (net (code "16") (name "Net-(TP10-1)") (class "Default")
      (node (ref "C14") (pin "1") (pinfunction "1_1") (pintype "passive"))
      (node (ref "TP10") (pin "P$1") (pinfunction "1_P$1") (pintype "bidirectional"))
    )
    (net (code "17") (name "Net-(TP11-1)") (class "Default")
      (node (ref "C15") (pin "1") (pinfunction "1_1") (pintype "passive"))
      (node (ref "TP11") (pin "P$1") (pinfunction "1_P$1") (pintype "bidirectional"))
    )
    (net (code "18") (name "Net-(TP12-1)") (class "Default")
      (node (ref "C16") (pin "1") (pinfunction "1_1") (pintype "passive"))
      (node (ref "TP12") (pin "P$1") (pinfunction "1_P$1") (pintype "bidirectional"))
    )
    (net (code "19") (name "Net-(TP13-1)") (class "Default")
      (node (ref "C17") (pin "1") (pinfunction "1_1") (pintype "passive"))
      (node (ref "TP13") (pin "P$1") (pinfunction "1_P$1") (pintype "bidirectional"))
    )
    (net (code "20") (name "Net-(TP14-1)") (class "Default")
      (node (ref "C18") (pin "+") (pinfunction "+_+") (pintype "passive"))
      (node (ref "TP14") (pin "P$1") (pinfunction "1_P$1") (pintype "bidirectional"))
    )
    (net (code "21") (name "Net-(TP15-1)") (class "Default")
      (node (ref "C12") (pin "2") (pinfunction "2_2") (pintype "passive"))
      (node (ref "TP15") (pin "P$1") (pinfunction "1_P$1") (pintype "bidirectional"))
    )
    (net (code "22") (name "Net-(TP16-1)") (class "Default")
      (node (ref "C13") (pin "2") (pinfunction "2_2") (pintype "passive"))
      (node (ref "TP16") (pin "P$1") (pinfunction "1_P$1") (pintype "bidirectional"))
    )
    (net (code "23") (name "Net-(TP17-1)") (class "Default")
      (node (ref "C14") (pin "2") (pinfunction "2_2") (pintype "passive"))
      (node (ref "TP17") (pin "P$1") (pinfunction "1_P$1") (pintype "bidirectional"))
    )
    (net (code "24") (name "Net-(TP18-1)") (class "Default")
      (node (ref "C15") (pin "2") (pinfunction "2_2") (pintype "passive"))
      (node (ref "TP18") (pin "P$1") (pinfunction "1_P$1") (pintype "bidirectional"))
    )
    (net (code "25") (name "Net-(TP19-1)") (class "Default")
      (node (ref "C16") (pin "2") (pinfunction "2_2") (pintype "passive"))
      (node (ref "TP19") (pin "P$1") (pinfunction "1_P$1") (pintype "bidirectional"))
    )
    (net (code "26") (name "Net-(TP20-1)") (class "Default")
      (node (ref "C17") (pin "2") (pinfunction "2_2") (pintype "passive"))
      (node (ref "TP20") (pin "P$1") (pinfunction "1_P$1") (pintype "bidirectional"))
    )
    (net (code "27") (name "Net-(TP21-1)") (class "Default")
      (node (ref "C18") (pin "-") (pinfunction "-_-") (pintype "passive"))
      (node (ref "TP21") (pin "P$1") (pinfunction "1_P$1") (pintype "bidirectional"))
    )
    (net (code "28") (name "Net-(TP22-1)") (class "Default")
      (node (ref "TP22") (pin "P$1") (pinfunction "1_P$1") (pintype "bidirectional"))
      (node (ref "TP33") (pin "P$1") (pinfunction "1_P$1") (pintype "bidirectional"))
    )
    (net (code "29") (name "Net-(TP23-1)") (class "Default")
      (node (ref "R4") (pin "1") (pinfunction "1_1") (pintype "passive"))
      (node (ref "TP23") (pin "P$1") (pinfunction "1_P$1") (pintype "bidirectional"))
    )
    (net (code "30") (name "Net-(TP24-1)") (class "Default")
      (node (ref "R6") (pin "2") (pinfunction "2_2") (pintype "passive"))
      (node (ref "R7") (pin "1") (pinfunction "1_1") (pintype "passive"))
      (node (ref "TP24") (pin "P$1") (pinfunction "1_P$1") (pintype "bidirectional"))
      (node (ref "TP28") (pin "P$1") (pinfunction "1_P$1") (pintype "bidirectional"))
    )
    (net (code "31") (name "Net-(TP25-1)") (class "Default")
      (node (ref "R10") (pin "1") (pinfunction "1_1") (pintype "passive"))
      (node (ref "R9") (pin "2") (pinfunction "2_2") (pintype "passive"))
      (node (ref "TP25") (pin "P$1") (pinfunction "1_P$1") (pintype "bidirectional"))
      (node (ref "TP31") (pin "P$1") (pinfunction "1_P$1") (pintype "bidirectional"))
    )
    (net (code "32") (name "Net-(TP26-1)") (class "Default")
      (node (ref "R4") (pin "2") (pinfunction "2_2") (pintype "passive"))
      (node (ref "R5") (pin "1") (pinfunction "1_1") (pintype "passive"))
      (node (ref "TP26") (pin "P$1") (pinfunction "1_P$1") (pintype "bidirectional"))
    )
    (net (code "33") (name "Net-(TP27-1)") (class "Default")
      (node (ref "R5") (pin "2") (pinfunction "2_2") (pintype "passive"))
      (node (ref "R6") (pin "1") (pinfunction "1_1") (pintype "passive"))
      (node (ref "TP27") (pin "P$1") (pinfunction "1_P$1") (pintype "bidirectional"))
    )
    (net (code "34") (name "Net-(TP29-1)") (class "Default")
      (node (ref "R7") (pin "2") (pinfunction "2_2") (pintype "passive"))
      (node (ref "R8") (pin "1") (pinfunction "1_1") (pintype "passive"))
      (node (ref "TP29") (pin "P$1") (pinfunction "1_P$1") (pintype "bidirectional"))
    )
    (net (code "35") (name "Net-(TP30-1)") (class "Default")
      (node (ref "R8") (pin "2") (pinfunction "2_2") (pintype "passive"))
      (node (ref "R9") (pin "1") (pinfunction "1_1") (pintype "passive"))
      (node (ref "TP30") (pin "P$1") (pinfunction "1_P$1") (pintype "bidirectional"))
    )
    (net (code "36") (name "Net-(TP32-1)") (class "Default")
      (node (ref "R12") (pin "2") (pinfunction "2_2") (pintype "passive"))
      (node (ref "R13") (pin "1") (pinfunction "1_1") (pintype "passive"))
      (node (ref "TP32") (pin "P$1") (pinfunction "1_P$1") (pintype "bidirectional"))
      (node (ref "TP36") (pin "P$1") (pinfunction "1_P$1") (pintype "bidirectional"))
    )
    (net (code "37") (name "Net-(TP34-1)") (class "Default")
      (node (ref "R10") (pin "2") (pinfunction "2_2") (pintype "passive"))
      (node (ref "R11") (pin "1") (pinfunction "1_1") (pintype "passive"))
      (node (ref "TP34") (pin "P$1") (pinfunction "1_P$1") (pintype "bidirectional"))
    )
    (net (code "38") (name "Net-(TP35-1)") (class "Default")
      (node (ref "R11") (pin "2") (pinfunction "2_2") (pintype "passive"))
      (node (ref "R12") (pin "1") (pinfunction "1_1") (pintype "passive"))
      (node (ref "TP35") (pin "P$1") (pinfunction "1_P$1") (pintype "bidirectional"))
    )
    (net (code "39") (name "Net-(TP37-1)") (class "Default")
      (node (ref "R13") (pin "2") (pinfunction "2_2") (pintype "passive"))
      (node (ref "R14") (pin "1") (pinfunction "1_1") (pintype "passive"))
      (node (ref "TP37") (pin "P$1") (pinfunction "1_P$1") (pintype "bidirectional"))
    )
    (net (code "40") (name "Net-(TP38-1)") (class "Default")
      (node (ref "R14") (pin "2") (pinfunction "2_2") (pintype "passive"))
      (node (ref "R15") (pin "1") (pinfunction "1_1") (pintype "passive"))
      (node (ref "TP38") (pin "P$1") (pinfunction "1_P$1") (pintype "bidirectional"))
    )
    (net (code "41") (name "Net-(TP39-1)") (class "Default")
      (node (ref "R15") (pin "2") (pinfunction "2_2") (pintype "passive"))
      (node (ref "TP39") (pin "P$1") (pinfunction "1_P$1") (pintype "bidirectional"))
    )
    (net (code "42") (name "Net-(TP40-1)") (class "Default")
      (node (ref "L1") (pin "1") (pinfunction "1_1") (pintype "passive"))
      (node (ref "TP40") (pin "P$1") (pinfunction "1_P$1") (pintype "bidirectional"))
    )
    (net (code "43") (name "Net-(TP41-1)") (class "Default")
      (node (ref "L2") (pin "1") (pinfunction "1_1") (pintype "passive"))
      (node (ref "TP41") (pin "P$1") (pinfunction "1_P$1") (pintype "bidirectional"))
    )
    (net (code "44") (name "Net-(TP42-1)") (class "Default")
      (node (ref "L3") (pin "1") (pinfunction "1_1") (pintype "passive"))
      (node (ref "TP42") (pin "P$1") (pinfunction "1_P$1") (pintype "bidirectional"))
    )
    (net (code "45") (name "Net-(TP43-1)") (class "Default")
      (node (ref "L4") (pin "1") (pinfunction "1_1") (pintype "passive"))
      (node (ref "TP43") (pin "P$1") (pinfunction "1_P$1") (pintype "bidirectional"))
    )
    (net (code "46") (name "Net-(TP44-1)") (class "Default")
      (node (ref "L5") (pin "1") (pinfunction "1_1") (pintype "passive"))
      (node (ref "TP44") (pin "P$1") (pinfunction "1_P$1") (pintype "bidirectional"))
    )
    (net (code "47") (name "Net-(TP45-1)") (class "Default")
      (node (ref "L1") (pin "2") (pinfunction "2_2") (pintype "passive"))
      (node (ref "TP45") (pin "P$1") (pinfunction "1_P$1") (pintype "bidirectional"))
    )
    (net (code "48") (name "Net-(TP46-1)") (class "Default")
      (node (ref "L2") (pin "2") (pinfunction "2_2") (pintype "passive"))
      (node (ref "TP46") (pin "P$1") (pinfunction "1_P$1") (pintype "bidirectional"))
    )
    (net (code "49") (name "Net-(TP47-1)") (class "Default")
      (node (ref "L3") (pin "2") (pinfunction "2_2") (pintype "passive"))
      (node (ref "TP47") (pin "P$1") (pinfunction "1_P$1") (pintype "bidirectional"))
    )
    (net (code "50") (name "Net-(TP48-1)") (class "Default")
      (node (ref "L4") (pin "2") (pinfunction "2_2") (pintype "passive"))
      (node (ref "TP48") (pin "P$1") (pinfunction "1_P$1") (pintype "bidirectional"))
    )
    (net (code "51") (name "Net-(TP49-1)") (class "Default")
      (node (ref "L5") (pin "2") (pinfunction "2_2") (pintype "passive"))
      (node (ref "TP49") (pin "P$1") (pinfunction "1_P$1") (pintype "bidirectional"))
    )
    (net (code "52") (name "Net-(U1-NR)") (class "Default")
      (node (ref "C4") (pin "1") (pinfunction "1_1") (pintype "passive"))
      (node (ref "U1") (pin "1") (pinfunction "NR_1") (pintype "passive"))
    )
    (net (code "53") (name "Net-(U2-NR)") (class "Default")
      (node (ref "C5") (pin "1") (pinfunction "1_1") (pintype "passive"))
      (node (ref "U2") (pin "1") (pinfunction "NR_1") (pintype "passive"))
    )
    (net (code "54") (name "Net-(U3-NR)") (class "Default")
      (node (ref "C6") (pin "1") (pinfunction "1_1") (pintype "passive"))
      (node (ref "U3") (pin "1") (pinfunction "NR_1") (pintype "passive"))
    )
    (net (code "55") (name "unconnected-(U1-I.C.-Pad8)") (class "Default")
      (node (ref "U1") (pin "8") (pinfunction "I.C._8") (pintype "passive"))
    )
    (net (code "56") (name "unconnected-(U1-I.C.2-Pad5)") (class "Default")
      (node (ref "U1") (pin "5") (pinfunction "I.C.2_5") (pintype "input"))
    )
    (net (code "57") (name "unconnected-(U2-I.C.-Pad8)") (class "Default")
      (node (ref "U2") (pin "8") (pinfunction "I.C._8") (pintype "passive"))
    )
    (net (code "58") (name "unconnected-(U2-I.C.2-Pad5)") (class "Default")
      (node (ref "U2") (pin "5") (pinfunction "I.C.2_5") (pintype "input"))
    )
    (net (code "59") (name "unconnected-(U3-I.C.-Pad8)") (class "Default")
      (node (ref "U3") (pin "8") (pinfunction "I.C._8") (pintype "passive"))
    )
    (net (code "60") (name "unconnected-(U3-I.C.2-Pad5)") (class "Default")
      (node (ref "U3") (pin "5") (pinfunction "I.C.2_5") (pintype "input"))
    )
  )
)
